# 8266_DIYIOT_Board_C_G_V_AS.net
KiCad netlist of a schematic drawn in EAGLE
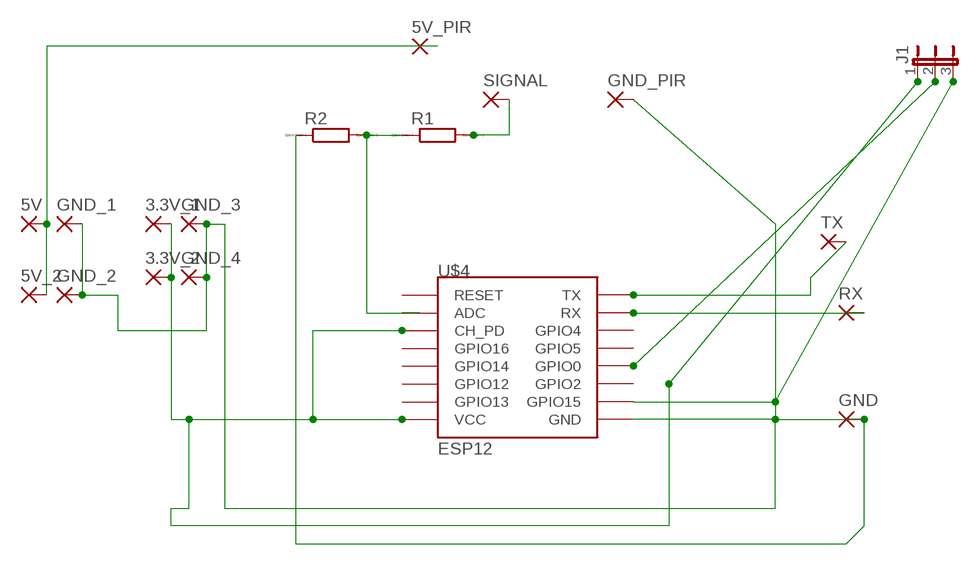
[diagram p0: schematic, sheet 1]

(export (version "E")
  (design (tool "Eeschema 10.0.6"))
  (components
    (comp (ref "3.3V_1")
      (value "2,15/1,0")
      (footprint "eagle-import:2,15_1,0")
      (libsource (lib "eagle-import") (part "2,15/1,0"))
    )
    (comp (ref "3.3V_2")
      (value "2,15/1,0")
      (footprint "eagle-import:2,15_1,0")
      (libsource (lib "eagle-import") (part "2,15/1,0"))
    )
    (comp (ref "5V")
      (value "2,15/1,0")
      (footprint "eagle-import:2,15_1,0")
      (libsource (lib "eagle-import") (part "2,15/1,0"))
    )
    (comp (ref "5V_2")
      (value "2,15/1,0")
      (footprint "eagle-import:2,15_1,0")
      (libsource (lib "eagle-import") (part "2,15/1,0"))
    )
    (comp (ref "5V_PIR")
      (value "2,15/1,0")
      (footprint "eagle-import:2,15_1,0")
      (libsource (lib "eagle-import") (part "2,15/1,0"))
    )
    (comp (ref "GND")
      (value "2,15/1,0")
      (footprint "eagle-import:2,15_1,0")
      (libsource (lib "eagle-import") (part "2,15/1,0"))
    )
    (comp (ref "GND_1")
      (value "2,15/1,0")
      (footprint "eagle-import:2,15_1,0")
      (libsource (lib "eagle-import") (part "2,15/1,0"))
    )
    (comp (ref "GND_2")
      (value "2,15/1,0")
      (footprint "eagle-import:2,15_1,0")
      (libsource (lib "eagle-import") (part "2,15/1,0"))
    )
    (comp (ref "GND_3")
      (value "2,15/1,0")
      (footprint "eagle-import:2,15_1,0")
      (libsource (lib "eagle-import") (part "2,15/1,0"))
    )
    (comp (ref "GND_4")
      (value "2,15/1,0")
      (footprint "eagle-import:2,15_1,0")
      (libsource (lib "eagle-import") (part "2,15/1,0"))
    )
    (comp (ref "GND_PIR")
      (value "2,15/1,0")
      (footprint "eagle-import:2,15_1,0")
      (libsource (lib "eagle-import") (part "2,15/1,0"))
    )
    (comp (ref "J1")
      (value "JP2E")
      (footprint "eagle-import:JP2")
      (libsource (lib "eagle-import") (part "JP2E"))
    )
    (comp (ref "R1")
      (value "R0204/7")
      (footprint "eagle-import:0204_7")
      (libsource (lib "eagle-import") (part "R0204/7"))
    )
    (comp (ref "R2")
      (value "R0204/7")
      (footprint "eagle-import:0204_7")
      (libsource (lib "eagle-import") (part "R0204/7"))
    )
    (comp (ref "RX")
      (value "2,15/1,0")
      (footprint "eagle-import:2,15_1,0")
      (libsource (lib "eagle-import") (part "2,15/1,0"))
    )
    (comp (ref "SIGNAL")
      (value "2,15/1,0")
      (footprint "eagle-import:2,15_1,0")
      (libsource (lib "eagle-import") (part "2,15/1,0"))
    )
    (comp (ref "TX")
      (value "2,15/1,0")
      (footprint "eagle-import:2,15_1,0")
      (libsource (lib "eagle-import") (part "2,15/1,0"))
    )
    (comp (ref "U$4")
      (value "ESP12")
      (footprint "eagle-import:ESP12")
      (libsource (lib "eagle-import") (part "ESP12"))
    )
  )
  (nets
    (net (code "1") (name "/5V") (class "Default")
      (node (ref "5V") (pin "1") (pinfunction "P_1") (pintype "passive"))
      (node (ref "5V_2") (pin "1") (pinfunction "P_1") (pintype "passive"))
      (node (ref "5V_PIR") (pin "1") (pinfunction "P_1") (pintype "passive"))
      (node (ref "GND") (pin "1") (pinfunction "P_1") (pintype "passive"))
      (node (ref "GND_1") (pin "1") (pinfunction "P_1") (pintype "passive"))
      (node (ref "GND_2") (pin "1") (pinfunction "P_1") (pintype "passive"))
      (node (ref "GND_3") (pin "1") (pinfunction "P_1") (pintype "passive"))
      (node (ref "GND_4") (pin "1") (pinfunction "P_1") (pintype "passive"))
      (node (ref "GND_PIR") (pin "1") (pinfunction "P_1") (pintype "passive"))
      (node (ref "J1") (pin "3") (pinfunction "3_3") (pintype "passive"))
      (node (ref "R2") (pin "1") (pinfunction "1_1") (pintype "passive"))
      (node (ref "U$4") (pin "GND") (pinfunction "GND_GND") (pintype "bidirectional"))
      (node (ref "U$4") (pin "GPIO15") (pinfunction "GPIO15_GPIO15") (pintype "bidirectional"))
    )
    (net (code "2") (name "Net-(3.3V_1-P)") (class "Default")
      (node (ref "3.3V_1") (pin "1") (pinfunction "P_1") (pintype "passive"))
      (node (ref "3.3V_2") (pin "1") (pinfunction "P_1") (pintype "passive"))
      (node (ref "J1") (pin "1") (pinfunction "1_1") (pintype "passive"))
      (node (ref "U$4") (pin "CH_PD") (pinfunction "CH_PD_CH_PD") (pintype "bidirectional"))
      (node (ref "U$4") (pin "VCC") (pinfunction "VCC_VCC") (pintype "bidirectional"))
    )
    (net (code "3") (name "Net-(J1-Pad2)") (class "Default")
      (node (ref "J1") (pin "2") (pinfunction "2_2") (pintype "passive"))
      (node (ref "U$4") (pin "GPIO0") (pinfunction "GPIO0_GPIO0") (pintype "bidirectional"))
    )
    (net (code "4") (name "Net-(R1-Pad1)") (class "Default")
      (node (ref "R1") (pin "1") (pinfunction "1_1") (pintype "passive"))
      (node (ref "R2") (pin "2") (pinfunction "2_2") (pintype "passive"))
      (node (ref "U$4") (pin "ADC") (pinfunction "ADC_ADC") (pintype "bidirectional"))
    )
    (net (code "5") (name "Net-(RX-P)") (class "Default")
      (node (ref "RX") (pin "1") (pinfunction "P_1") (pintype "passive"))
      (node (ref "U$4") (pin "RX") (pinfunction "RX_RX") (pintype "bidirectional"))
    )
    (net (code "6") (name "Net-(SIGNAL-P)") (class "Default")
      (node (ref "R1") (pin "2") (pinfunction "2_2") (pintype "passive"))
      (node (ref "SIGNAL") (pin "1") (pinfunction "P_1") (pintype "passive"))
    )
    (net (code "7") (name "Net-(TX-P)") (class "Default")
      (node (ref "TX") (pin "1") (pinfunction "P_1") (pintype "passive"))
      (node (ref "U$4") (pin "TX") (pinfunction "TX_TX") (pintype "bidirectional"))
    )
    (net (code "8") (name "unconnected-(U$4-PadGPIO2)") (class "Default")
      (node (ref "U$4") (pin "GPIO2") (pinfunction "GPIO2_GPIO2") (pintype "bidirectional"))
    )
    (net (code "9") (name "unconnected-(U$4-PadGPIO4)") (class "Default")
      (node (ref "U$4") (pin "GPIO4") (pinfunction "GPIO4_GPIO4") (pintype "bidirectional"))
    )
    (net (code "10") (name "unconnected-(U$4-PadGPIO5)") (class "Default")
      (node (ref "U$4") (pin "GPIO5") (pinfunction "GPIO5_GPIO5") (pintype "bidirectional"))
    )
    (net (code "11") (name "unconnected-(U$4-PadGPIO12)") (class "Default")
      (node (ref "U$4") (pin "GPIO12") (pinfunction "GPIO12_GPIO12") (pintype "bidirectional"))
    )
    (net (code "12") (name "unconnected-(U$4-PadGPIO13)") (class "Default")
      (node (ref "U$4") (pin "GPIO13") (pinfunction "GPIO13_GPIO13") (pintype "bidirectional"))
    )
    (net (code "13") (name "unconnected-(U$4-PadGPIO14)") (class "Default")
      (node (ref "U$4") (pin "GPIO14") (pinfunction "GPIO14_GPIO14") (pintype "bidirectional"))
    )
    (net (code "14") (name "unconnected-(U$4-PadGPIO16)") (class "Default")
      (node (ref "U$4") (pin "GPIO16") (pinfunction "GPIO16_GPIO16") (pintype "bidirectional"))
    )
    (net (code "15") (name "unconnected-(U$4-PadRESET)") (class "Default")
      (node (ref "U$4") (pin "RESET") (pinfunction "RESET_RESET") (pintype "bidirectional"))
    )
  )
)
